# pcb-exp_rience.net
KiCad netlist of a schematic drawn in EAGLE
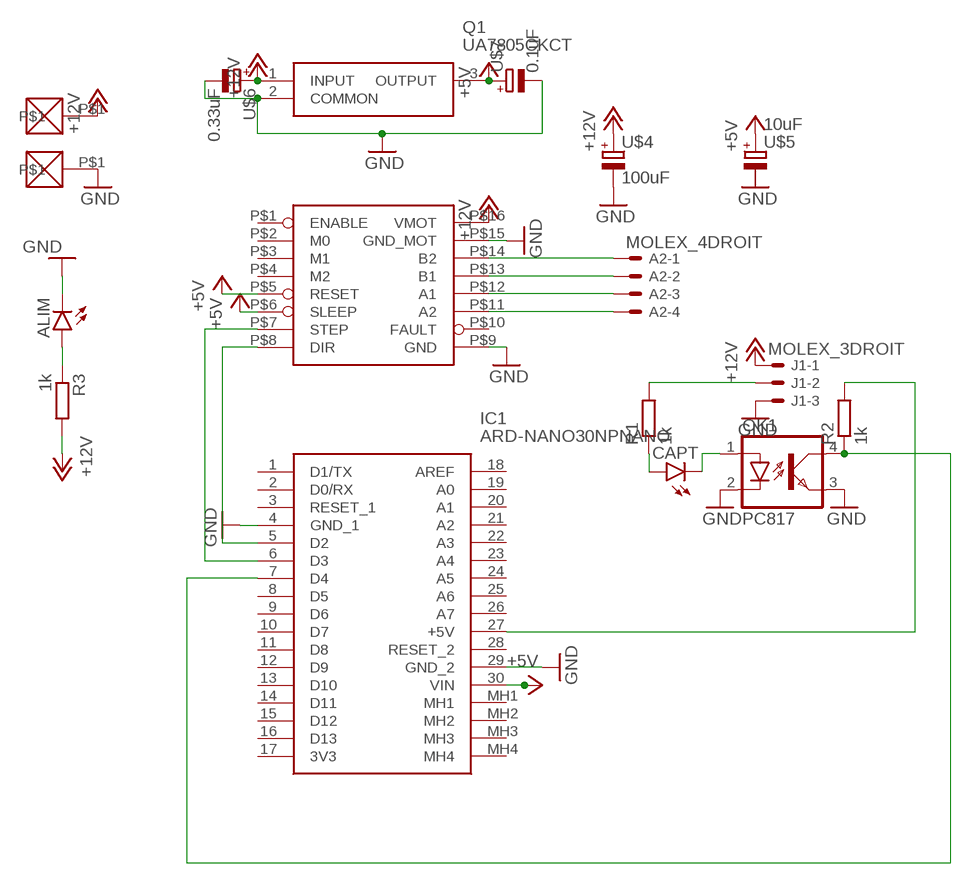
[diagram p0: schematic, sheet 1]

(export (version "E")
  (design (tool "Eeschema 10.0.6"))
  (components
    (comp (ref "A2")
      (value "MOLEX_4DROIT")
      (footprint "eagle-import:CON_4_DROIT")
      (fields (field (name "MF") "MOLEX"))
      (libsource (lib "eagle-import") (part "MOLEX_4DROIT"))
    )
    (comp (ref "ALIM")
      (value "LED5MM")
      (footprint "eagle-import:LED5MM")
      (libsource (lib "eagle-import") (part "LED5MM"))
    )
    (comp (ref "CAPT")
      (value "LED5MM")
      (footprint "eagle-import:LED5MM")
      (libsource (lib "eagle-import") (part "LED5MM"))
    )
    (comp (ref "IC1")
      (value "ARD-NANO30NPNANO")
      (footprint "eagle-import:ARDNANO30NP")
      (fields
        (field (name "MANUFACTURER_PART_NUMBER") "ARD-NANO30NP")
        (field (name "MOUSER_PART_NUMBER") "992-ARD-NANO30NP")
      )
      (libsource (lib "eagle-import") (part "ARD-NANO30NPNANO"))
    )
    (comp (ref "J1")
      (value "MOLEX_3DROIT")
      (footprint "eagle-import:CON_3_DROIT")
      (fields (field (name "MF") "MOLEX"))
      (libsource (lib "eagle-import") (part "MOLEX_3DROIT"))
    )
    (comp (ref "OK1")
      (value "PC817")
      (footprint "eagle-import:DIL04")
      (fields (field (name "MPN") "PC817X4J000F"))
      (libsource (lib "eagle-import") (part "PC817"))
    )
    (comp (ref "Q1")
      (value "UA7805CKCT")
      (footprint "eagle-import:TO254P465X1016X1883-3P")
      (fields (field (name "MOUSER_PART_NUMBER") "595-UA7805CKCT") (field (name "RS_PART_NUMBER") "8100161"))
      (libsource (lib "eagle-import") (part "UA7805CKCT"))
    )
    (comp (ref "R1")
      (value "1k")
      (footprint "eagle-import:0207_2V")
      (libsource (lib "eagle-import") (part "R-EU_0207/2V"))
    )
    (comp (ref "R2")
      (value "1k")
      (footprint "eagle-import:0207_7")
      (libsource (lib "eagle-import") (part "R-EU_0207/7"))
    )
    (comp (ref "R3")
      (value "1k")
      (footprint "eagle-import:0207_2V")
      (libsource (lib "eagle-import") (part "R-EU_0207/2V"))
    )
    (comp (ref "U$1")
      (value "DRV8825")
      (footprint "eagle-import:DRV8825")
      (libsource (lib "eagle-import") (part "DRV8825"))
    )
    (comp (ref "U$2")
      (value "BAT_WIRE_SOLD")
      (footprint "eagle-import:LARGE_PAD_BATT")
      (libsource (lib "eagle-import") (part "BAT_WIRE_SOLD"))
    )
    (comp (ref "U$3")
      (value "BAT_WIRE_SOLD")
      (footprint "eagle-import:LARGE_PAD_BATT")
      (libsource (lib "eagle-import") (part "BAT_WIRE_SOLD"))
    )
    (comp (ref "U$4")
      (value "100uF")
      (footprint "eagle-import:E3,5-8")
      (libsource (lib "eagle-import") (part "CONDO3.5-8"))
    )
    (comp (ref "U$5")
      (value "10uF")
      (footprint "eagle-import:E2-5")
      (libsource (lib "eagle-import") (part "CONDO2-5"))
    )
    (comp (ref "U$6")
      (value "0.33uF")
      (footprint "eagle-import:E2-5")
      (libsource (lib "eagle-import") (part "CONDO2-5"))
    )
    (comp (ref "U$7")
      (value "0.1uF")
      (footprint "eagle-import:E2-5")
      (libsource (lib "eagle-import") (part "CONDO2-5"))
    )
  )
  (nets
    (net (code "1") (name "+5V") (class "Default")
      (node (ref "IC1") (pin "30") (pinfunction "VIN_30") (pintype "bidirectional"))
      (node (ref "Q1") (pin "3") (pinfunction "OUTPUT_3") (pintype "output"))
      (node (ref "U$1") (pin "P$5") (pinfunction "RESET_P$5") (pintype "bidirectional"))
      (node (ref "U$1") (pin "P$6") (pinfunction "SLEEP_P$6") (pintype "bidirectional"))
      (node (ref "U$5") (pin "+") (pinfunction "+_+") (pintype "passive"))
      (node (ref "U$7") (pin "+") (pinfunction "+_+") (pintype "passive"))
    )
    (net (code "2") (name "+12V") (class "Default")
      (node (ref "J1") (pin "1") (pinfunction "S_1") (pintype "passive"))
      (node (ref "Q1") (pin "1") (pinfunction "INPUT_1") (pintype "input"))
      (node (ref "R3") (pin "2") (pinfunction "2_2") (pintype "passive"))
      (node (ref "U$1") (pin "P$16") (pinfunction "VMOT_P$16") (pintype "bidirectional"))
      (node (ref "U$2") (pin "P$1") (pinfunction "P$1_P$1") (pintype "bidirectional"))
      (node (ref "U$4") (pin "+") (pinfunction "+_+") (pintype "passive"))
      (node (ref "U$6") (pin "+") (pinfunction "+_+") (pintype "passive"))
    )
    (net (code "3") (name "GND") (class "Default")
      (node (ref "ALIM") (pin "K") (pinfunction "C_K") (pintype "passive"))
      (node (ref "IC1") (pin "29") (pinfunction "GND_2_29") (pintype "bidirectional"))
      (node (ref "IC1") (pin "4") (pinfunction "GND_1_4") (pintype "bidirectional"))
      (node (ref "J1") (pin "3") (pinfunction "S_3") (pintype "passive"))
      (node (ref "OK1") (pin "2") (pinfunction "C_2") (pintype "passive"))
      (node (ref "OK1") (pin "3") (pinfunction "EMIT_3") (pintype "passive"))
      (node (ref "Q1") (pin "2") (pinfunction "COMMON_2") (pintype "power_in"))
      (node (ref "U$1") (pin "P$15") (pinfunction "GND_MOT_P$15") (pintype "bidirectional"))
      (node (ref "U$1") (pin "P$9") (pinfunction "GND_P$9") (pintype "bidirectional"))
      (node (ref "U$3") (pin "P$1") (pinfunction "P$1_P$1") (pintype "bidirectional"))
      (node (ref "U$4") (pin "-") (pinfunction "-_-") (pintype "passive"))
      (node (ref "U$6") (pin "-") (pinfunction "-_-") (pintype "passive"))
      (node (ref "U$7") (pin "-") (pinfunction "-_-") (pintype "passive"))
    )
    (net (code "4") (name "Net-(A2A-S)") (class "Default")
      (node (ref "A2") (pin "1") (pinfunction "S_1") (pintype "passive"))
      (node (ref "U$1") (pin "P$14") (pinfunction "B2_P$14") (pintype "bidirectional"))
    )
    (net (code "5") (name "Net-(A2B-S)") (class "Default")
      (node (ref "A2") (pin "2") (pinfunction "S_2") (pintype "passive"))
      (node (ref "U$1") (pin "P$13") (pinfunction "B1_P$13") (pintype "bidirectional"))
    )
    (net (code "6") (name "Net-(A2C-S)") (class "Default")
      (node (ref "A2") (pin "3") (pinfunction "S_3") (pintype "passive"))
      (node (ref "U$1") (pin "P$12") (pinfunction "A1_P$12") (pintype "bidirectional"))
    )
    (net (code "7") (name "Net-(A2D-S)") (class "Default")
      (node (ref "A2") (pin "4") (pinfunction "S_4") (pintype "passive"))
      (node (ref "U$1") (pin "P$11") (pinfunction "A2_P$11") (pintype "bidirectional"))
    )
    (net (code "8") (name "Net-(ALIM-PadA)") (class "Default")
      (node (ref "ALIM") (pin "A") (pinfunction "A_A") (pintype "passive"))
      (node (ref "R3") (pin "1") (pinfunction "1_1") (pintype "passive"))
    )
    (net (code "9") (name "Net-(CAPT-C)") (class "Default")
      (node (ref "CAPT") (pin "K") (pinfunction "C_K") (pintype "passive"))
      (node (ref "OK1") (pin "1") (pinfunction "A_1") (pintype "passive"))
    )
    (net (code "10") (name "Net-(CAPT-PadA)") (class "Default")
      (node (ref "CAPT") (pin "A") (pinfunction "A_A") (pintype "passive"))
      (node (ref "R1") (pin "1") (pinfunction "1_1") (pintype "passive"))
    )
    (net (code "11") (name "Net-(IC1-+5V)") (class "Default")
      (node (ref "IC1") (pin "27") (pinfunction "+5V_27") (pintype "bidirectional"))
      (node (ref "R2") (pin "2") (pinfunction "2_2") (pintype "passive"))
    )
    (net (code "12") (name "Net-(IC1-D2)") (class "Default")
      (node (ref "IC1") (pin "5") (pinfunction "D2_5") (pintype "bidirectional"))
      (node (ref "U$1") (pin "P$8") (pinfunction "DIR_P$8") (pintype "bidirectional"))
    )
    (net (code "13") (name "Net-(IC1-D3)") (class "Default")
      (node (ref "IC1") (pin "6") (pinfunction "D3_6") (pintype "bidirectional"))
      (node (ref "U$1") (pin "P$7") (pinfunction "STEP_P$7") (pintype "bidirectional"))
    )
    (net (code "14") (name "Net-(IC1-D4)") (class "Default")
      (node (ref "IC1") (pin "7") (pinfunction "D4_7") (pintype "bidirectional"))
      (node (ref "OK1") (pin "4") (pinfunction "COL_4") (pintype "passive"))
      (node (ref "R2") (pin "1") (pinfunction "1_1") (pintype "passive"))
    )
    (net (code "15") (name "Net-(J1B-S)") (class "Default")
      (node (ref "J1") (pin "2") (pinfunction "S_2") (pintype "passive"))
      (node (ref "R1") (pin "2") (pinfunction "2_2") (pintype "passive"))
    )
    (net (code "16") (name "unconnected-(IC1-3V3-Pad17)") (class "Default")
      (node (ref "IC1") (pin "17") (pinfunction "3V3_17") (pintype "bidirectional"))
    )
    (net (code "17") (name "unconnected-(IC1-A0-Pad19)") (class "Default")
      (node (ref "IC1") (pin "19") (pinfunction "A0_19") (pintype "bidirectional"))
    )
    (net (code "18") (name "unconnected-(IC1-A1-Pad20)") (class "Default")
      (node (ref "IC1") (pin "20") (pinfunction "A1_20") (pintype "bidirectional"))
    )
    (net (code "19") (name "unconnected-(IC1-A2-Pad21)") (class "Default")
      (node (ref "IC1") (pin "21") (pinfunction "A2_21") (pintype "bidirectional"))
    )
    (net (code "20") (name "unconnected-(IC1-A3-Pad22)") (class "Default")
      (node (ref "IC1") (pin "22") (pinfunction "A3_22") (pintype "bidirectional"))
    )
    (net (code "21") (name "unconnected-(IC1-A4-Pad23)") (class "Default")
      (node (ref "IC1") (pin "23") (pinfunction "A4_23") (pintype "bidirectional"))
    )
    (net (code "22") (name "unconnected-(IC1-A5-Pad24)") (class "Default")
      (node (ref "IC1") (pin "24") (pinfunction "A5_24") (pintype "bidirectional"))
    )
    (net (code "23") (name "unconnected-(IC1-A6-Pad25)") (class "Default")
      (node (ref "IC1") (pin "25") (pinfunction "A6_25") (pintype "bidirectional"))
    )
    (net (code "24") (name "unconnected-(IC1-A7-Pad26)") (class "Default")
      (node (ref "IC1") (pin "26") (pinfunction "A7_26") (pintype "bidirectional"))
    )
    (net (code "25") (name "unconnected-(IC1-AREF-Pad18)") (class "Default")
      (node (ref "IC1") (pin "18") (pinfunction "AREF_18") (pintype "bidirectional"))
    )
    (net (code "26") (name "unconnected-(IC1-D0{slash}RX-Pad2)") (class "Default")
      (node (ref "IC1") (pin "2") (pinfunction "D0/RX_2") (pintype "bidirectional"))
    )
    (net (code "27") (name "unconnected-(IC1-D1{slash}TX-Pad1)") (class "Default")
      (node (ref "IC1") (pin "1") (pinfunction "D1/TX_1") (pintype "bidirectional"))
    )
    (net (code "28") (name "unconnected-(IC1-D5-Pad8)") (class "Default")
      (node (ref "IC1") (pin "8") (pinfunction "D5_8") (pintype "bidirectional"))
    )
    (net (code "29") (name "unconnected-(IC1-D6-Pad9)") (class "Default")
      (node (ref "IC1") (pin "9") (pinfunction "D6_9") (pintype "bidirectional"))
    )
    (net (code "30") (name "unconnected-(IC1-D7-Pad10)") (class "Default")
      (node (ref "IC1") (pin "10") (pinfunction "D7_10") (pintype "bidirectional"))
    )
    (net (code "31") (name "unconnected-(IC1-D8-Pad11)") (class "Default")
      (node (ref "IC1") (pin "11") (pinfunction "D8_11") (pintype "bidirectional"))
    )
    (net (code "32") (name "unconnected-(IC1-D9-Pad12)") (class "Default")
      (node (ref "IC1") (pin "12") (pinfunction "D9_12") (pintype "bidirectional"))
    )
    (net (code "33") (name "unconnected-(IC1-D10-Pad13)") (class "Default")
      (node (ref "IC1") (pin "13") (pinfunction "D10_13") (pintype "bidirectional"))
    )
    (net (code "34") (name "unconnected-(IC1-D11-Pad14)") (class "Default")
      (node (ref "IC1") (pin "14") (pinfunction "D11_14") (pintype "bidirectional"))
    )
    (net (code "35") (name "unconnected-(IC1-D12-Pad15)") (class "Default")
      (node (ref "IC1") (pin "15") (pinfunction "D12_15") (pintype "bidirectional"))
    )
    (net (code "36") (name "unconnected-(IC1-D13-Pad16)") (class "Default")
      (node (ref "IC1") (pin "16") (pinfunction "D13_16") (pintype "bidirectional"))
    )
    (net (code "37") (name "unconnected-(IC1-PadMH1)") (class "Default")
      (node (ref "IC1") (pin "MH1") (pinfunction "MH1_MH1") (pintype "bidirectional"))
    )
    (net (code "38") (name "unconnected-(IC1-PadMH2)") (class "Default")
      (node (ref "IC1") (pin "MH2") (pinfunction "MH2_MH2") (pintype "bidirectional"))
    )
    (net (code "39") (name "unconnected-(IC1-PadMH3)") (class "Default")
      (node (ref "IC1") (pin "MH3") (pinfunction "MH3_MH3") (pintype "bidirectional"))
    )
    (net (code "40") (name "unconnected-(IC1-PadMH4)") (class "Default")
      (node (ref "IC1") (pin "MH4") (pinfunction "MH4_MH4") (pintype "bidirectional"))
    )
    (net (code "41") (name "unconnected-(IC1-RESET_1-Pad3)") (class "Default")
      (node (ref "IC1") (pin "3") (pinfunction "RESET_1_3") (pintype "bidirectional"))
    )
    (net (code "42") (name "unconnected-(IC1-RESET_2-Pad28)") (class "Default")
      (node (ref "IC1") (pin "28") (pinfunction "RESET_2_28") (pintype "bidirectional"))
    )
    (net (code "43") (name "unconnected-(U$1-ENABLE-PadP$1)") (class "Default")
      (node (ref "U$1") (pin "P$1") (pinfunction "ENABLE_P$1") (pintype "bidirectional"))
    )
    (net (code "44") (name "unconnected-(U$1-FAULT-PadP$10)") (class "Default")
      (node (ref "U$1") (pin "P$10") (pinfunction "FAULT_P$10") (pintype "bidirectional"))
    )
    (net (code "45") (name "unconnected-(U$1-M0-PadP$2)") (class "Default")
      (node (ref "U$1") (pin "P$2") (pinfunction "M0_P$2") (pintype "bidirectional"))
    )
    (net (code "46") (name "unconnected-(U$1-M1-PadP$3)") (class "Default")
      (node (ref "U$1") (pin "P$3") (pinfunction "M1_P$3") (pintype "bidirectional"))
    )
    (net (code "47") (name "unconnected-(U$1-M2-PadP$4)") (class "Default")
      (node (ref "U$1") (pin "P$4") (pinfunction "M2_P$4") (pintype "bidirectional"))
    )
    (net (code "48") (name "unconnected-(U$5-Pad-)") (class "Default")
      (node (ref "U$5") (pin "-") (pinfunction "-_-") (pintype "passive"))
    )
  )
)
